# Fpga.net
KiCad netlist of a schematic drawn in Altium Designer
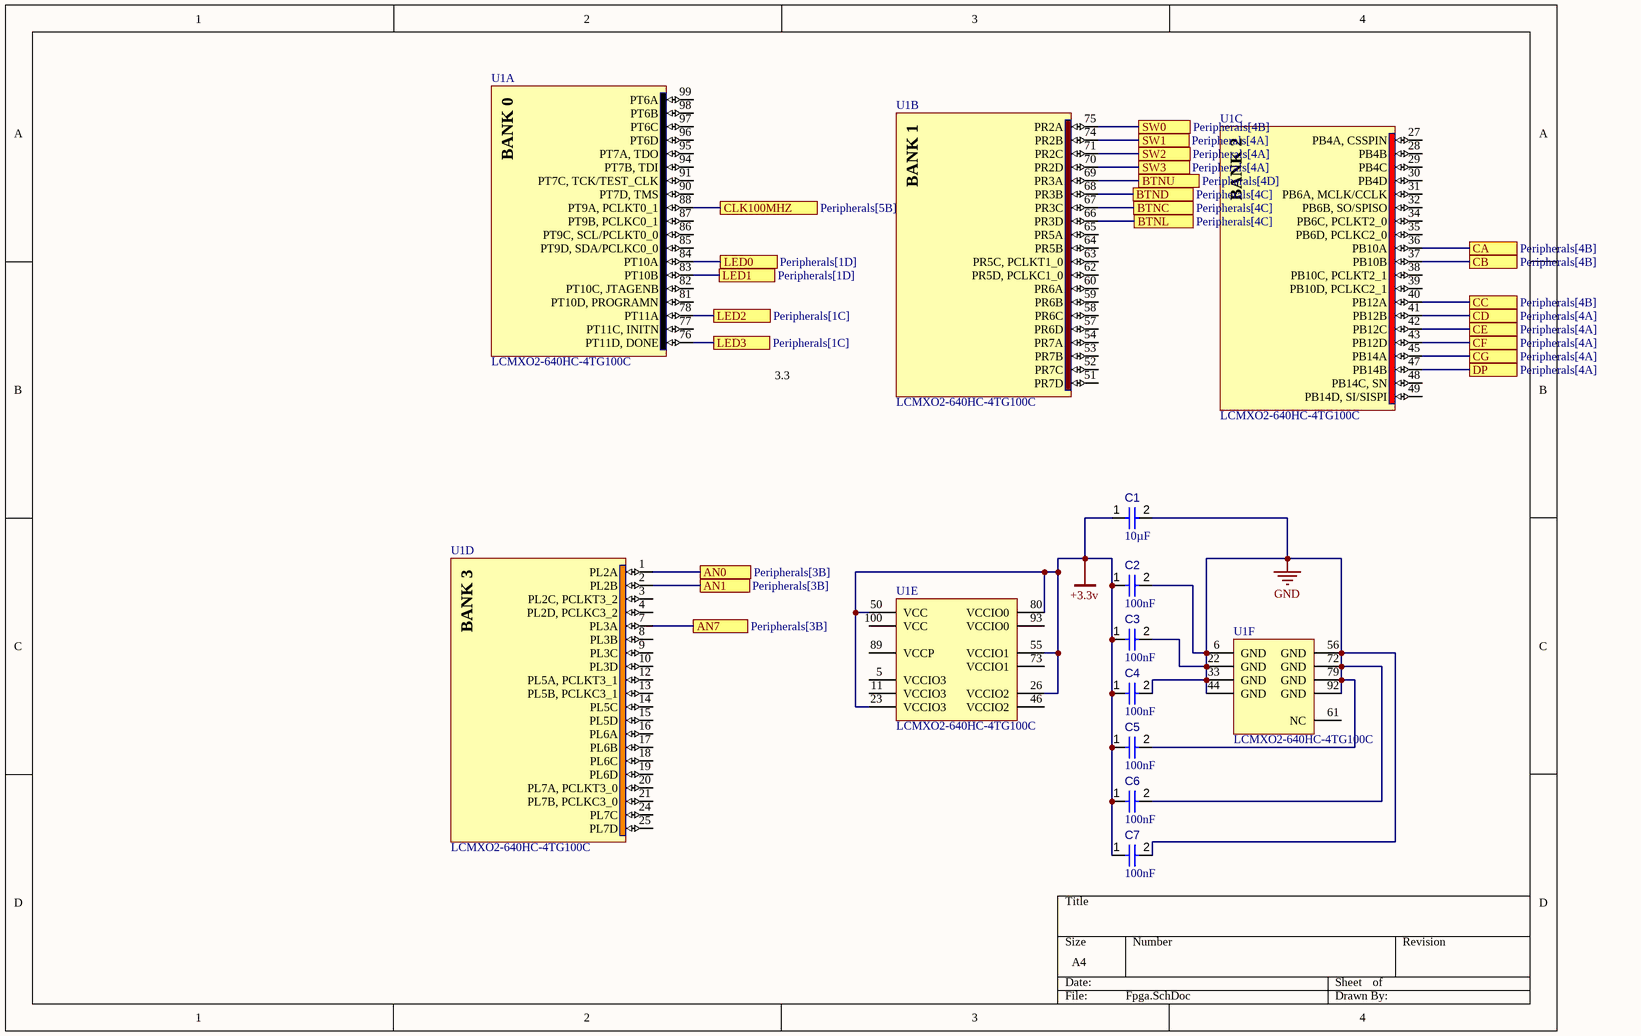
[diagram p0: Fpga.SchDoc]

(export (version "E")
  (design (tool "Eeschema 10.0.6"))
  (components
    (comp (ref "C1")
      (value "10µF")
      (footprint "CAPC0805(2012)145_L")
      (description "Chip Capacitor, 10µF +/-20%, 25V, 0805, Thickness 1.45 mm")
      (fields (field (name "TOLERANCE") "10%") (field (name "Comment") "Capacitor 10µF +/-20% 25V 0805"))
      (libsource (lib "Md-arman-zaid Efty") (part "CAP-NP-2"))
    )
    (comp (ref "C2")
      (value "100nF")
      (footprint "CAPC0402(1005)60_L")
      (description "Chip Capacitor, 100nF +/-20%, 10V, 0402, Thickness 0.6 mm")
      (fields (field (name "TOLERANCE") "20%") (field (name "Comment") "Capacitor 100nF +/-20% 10V 0402"))
      (libsource (lib "Md-arman-zaid Efty") (part "CAP-NP-2"))
    )
    (comp (ref "C3")
      (value "100nF")
      (footprint "CAPC0402(1005)60_L")
      (description "Chip Capacitor, 100nF +/-20%, 10V, 0402, Thickness 0.6 mm")
      (fields (field (name "TOLERANCE") "20%") (field (name "Comment") "Capacitor 100nF +/-20% 10V 0402"))
      (libsource (lib "Md-arman-zaid Efty") (part "CAP-NP-2"))
    )
    (comp (ref "C4")
      (value "100nF")
      (footprint "CAPC0402(1005)60_L")
      (description "Chip Capacitor, 100nF +/-20%, 10V, 0402, Thickness 0.6 mm")
      (fields (field (name "TOLERANCE") "20%") (field (name "Comment") "Capacitor 100nF +/-20% 10V 0402"))
      (libsource (lib "Md-arman-zaid Efty") (part "CAP-NP-2"))
    )
    (comp (ref "C5")
      (value "100nF")
      (footprint "CAPC0402(1005)60_L")
      (description "Chip Capacitor, 100nF +/-20%, 10V, 0402, Thickness 0.6 mm")
      (fields (field (name "TOLERANCE") "20%") (field (name "Comment") "Capacitor 100nF +/-20% 10V 0402"))
      (libsource (lib "Md-arman-zaid Efty") (part "CAP-NP-2"))
    )
    (comp (ref "C6")
      (value "100nF")
      (footprint "CAPC0402(1005)60_L")
      (description "Chip Capacitor, 100nF +/-20%, 10V, 0402, Thickness 0.6 mm")
      (fields (field (name "TOLERANCE") "20%") (field (name "Comment") "Capacitor 100nF +/-20% 10V 0402"))
      (libsource (lib "Md-arman-zaid Efty") (part "CAP-NP-2"))
    )
    (comp (ref "C7")
      (value "100nF")
      (footprint "CAPC0402(1005)60_L")
      (description "Chip Capacitor, 100nF +/-20%, 10V, 0402, Thickness 0.6 mm")
      (fields (field (name "TOLERANCE") "20%") (field (name "Comment") "Capacitor 100nF +/-20% 10V 0402"))
      (libsource (lib "Md-arman-zaid Efty") (part "CAP-NP-2"))
    )
    (comp (ref "U1")
      (value "LCMXO2-640HC-4TG100C")
      (footprint "TQFP100_M")
      (libsource (lib "Altium Content Vault") (part "PLD-LTMXO2-640-TQ100"))
    )
  )
  (nets
    (net (code "1") (name "+3.3v") (class "Default")
      (node (ref "C1") (pin "1") (pinfunction "1_1") (pintype "passive"))
      (node (ref "C2") (pin "1") (pinfunction "1_1") (pintype "passive"))
      (node (ref "C3") (pin "1") (pinfunction "1_1") (pintype "passive"))
      (node (ref "C4") (pin "1") (pinfunction "1_1") (pintype "passive"))
      (node (ref "C5") (pin "1") (pinfunction "1_1") (pintype "passive"))
      (node (ref "C6") (pin "1") (pinfunction "1_1") (pintype "passive"))
      (node (ref "C7") (pin "1") (pinfunction "1_1") (pintype "passive"))
      (node (ref "U1") (pin "23") (pinfunction "VCCIO3_23") (pintype "power_in"))
      (node (ref "U1") (pin "26") (pinfunction "VCCIO2_26") (pintype "power_in"))
      (node (ref "U1") (pin "50") (pinfunction "VCC_50") (pintype "power_in"))
      (node (ref "U1") (pin "55") (pinfunction "VCCIO1_55") (pintype "power_in"))
      (node (ref "U1") (pin "80") (pinfunction "VCCIO0_80") (pintype "power_in"))
    )
    (net (code "2") (name "/AN0") (class "Default")
      (node (ref "U1") (pin "1") (pinfunction "PL2A_1") (pintype "bidirectional"))
    )
    (net (code "3") (name "/AN1") (class "Default")
      (node (ref "U1") (pin "2") (pinfunction "PL2B_2") (pintype "bidirectional"))
    )
    (net (code "4") (name "/AN7") (class "Default")
      (node (ref "U1") (pin "7") (pinfunction "PL3A_7") (pintype "bidirectional"))
    )
    (net (code "5") (name "/BTNC") (class "Default")
      (node (ref "U1") (pin "67") (pinfunction "PR3C_67") (pintype "bidirectional"))
    )
    (net (code "6") (name "/BTND") (class "Default")
      (node (ref "U1") (pin "68") (pinfunction "PR3B_68") (pintype "bidirectional"))
    )
    (net (code "7") (name "/BTNL") (class "Default")
      (node (ref "U1") (pin "66") (pinfunction "PR3D_66") (pintype "bidirectional"))
    )
    (net (code "8") (name "/BTNU") (class "Default")
      (node (ref "U1") (pin "69") (pinfunction "PR3A_69") (pintype "bidirectional"))
    )
    (net (code "9") (name "/CA") (class "Default")
      (node (ref "U1") (pin "36") (pinfunction "PB10A_36") (pintype "bidirectional"))
    )
    (net (code "10") (name "/CB") (class "Default")
      (node (ref "U1") (pin "37") (pinfunction "PB10B_37") (pintype "bidirectional"))
    )
    (net (code "11") (name "/CC") (class "Default")
      (node (ref "U1") (pin "40") (pinfunction "PB12A_40") (pintype "bidirectional"))
    )
    (net (code "12") (name "/CD") (class "Default")
      (node (ref "U1") (pin "41") (pinfunction "PB12B_41") (pintype "bidirectional"))
    )
    (net (code "13") (name "/CE") (class "Default")
      (node (ref "U1") (pin "42") (pinfunction "PB12C_42") (pintype "bidirectional"))
    )
    (net (code "14") (name "/CF") (class "Default")
      (node (ref "U1") (pin "43") (pinfunction "PB12D_43") (pintype "bidirectional"))
    )
    (net (code "15") (name "/CG") (class "Default")
      (node (ref "U1") (pin "45") (pinfunction "PB14A_45") (pintype "bidirectional"))
    )
    (net (code "16") (name "/CLK100MHZ") (class "Default")
      (node (ref "U1") (pin "88") (pinfunction "PT9A,_PCLKT0_1_88") (pintype "bidirectional"))
    )
    (net (code "17") (name "/DP") (class "Default")
      (node (ref "U1") (pin "47") (pinfunction "PB14B_47") (pintype "bidirectional"))
    )
    (net (code "18") (name "/LED0") (class "Default")
      (node (ref "U1") (pin "84") (pinfunction "PT10A_84") (pintype "bidirectional"))
    )
    (net (code "19") (name "/LED1") (class "Default")
      (node (ref "U1") (pin "83") (pinfunction "PT10B_83") (pintype "bidirectional"))
    )
    (net (code "20") (name "/LED2") (class "Default")
      (node (ref "U1") (pin "78") (pinfunction "PT11A_78") (pintype "bidirectional"))
    )
    (net (code "21") (name "/LED3") (class "Default")
      (node (ref "U1") (pin "76") (pinfunction "PT11D,_DONE_76") (pintype "bidirectional"))
    )
    (net (code "22") (name "/SW0") (class "Default")
      (node (ref "U1") (pin "75") (pinfunction "PR2A_75") (pintype "bidirectional"))
    )
    (net (code "23") (name "/SW1") (class "Default")
      (node (ref "U1") (pin "74") (pinfunction "PR2B_74") (pintype "bidirectional"))
    )
    (net (code "24") (name "/SW2") (class "Default")
      (node (ref "U1") (pin "71") (pinfunction "PR2C_71") (pintype "bidirectional"))
    )
    (net (code "25") (name "/SW3") (class "Default")
      (node (ref "U1") (pin "70") (pinfunction "PR2D_70") (pintype "bidirectional"))
    )
    (net (code "26") (name "GND") (class "Default")
      (node (ref "C1") (pin "2") (pinfunction "2_2") (pintype "passive"))
      (node (ref "C2") (pin "2") (pinfunction "2_2") (pintype "passive"))
      (node (ref "C3") (pin "2") (pinfunction "2_2") (pintype "passive"))
      (node (ref "C4") (pin "2") (pinfunction "2_2") (pintype "passive"))
      (node (ref "C5") (pin "2") (pinfunction "2_2") (pintype "passive"))
      (node (ref "C6") (pin "2") (pinfunction "2_2") (pintype "passive"))
      (node (ref "C7") (pin "2") (pinfunction "2_2") (pintype "passive"))
      (node (ref "U1") (pin "22") (pinfunction "GND_22") (pintype "power_in"))
      (node (ref "U1") (pin "33") (pinfunction "GND_33") (pintype "power_in"))
      (node (ref "U1") (pin "44") (pinfunction "GND_44") (pintype "power_in"))
      (node (ref "U1") (pin "56") (pinfunction "GND_56") (pintype "power_in"))
      (node (ref "U1") (pin "6") (pinfunction "GND_6") (pintype "power_in"))
      (node (ref "U1") (pin "72") (pinfunction "GND_72") (pintype "power_in"))
      (node (ref "U1") (pin "79") (pinfunction "GND_79") (pintype "power_in"))
      (node (ref "U1") (pin "92") (pinfunction "GND_92") (pintype "power_in"))
    )
    (net (code "27") (name "unconnected-(U1A-PT6A-Pad99)") (class "Default")
      (node (ref "U1") (pin "99") (pinfunction "PT6A_99") (pintype "bidirectional"))
    )
    (net (code "28") (name "unconnected-(U1A-PT6B-Pad98)") (class "Default")
      (node (ref "U1") (pin "98") (pinfunction "PT6B_98") (pintype "bidirectional"))
    )
    (net (code "29") (name "unconnected-(U1A-PT6C-Pad97)") (class "Default")
      (node (ref "U1") (pin "97") (pinfunction "PT6C_97") (pintype "bidirectional"))
    )
    (net (code "30") (name "unconnected-(U1A-PT6D-Pad96)") (class "Default")
      (node (ref "U1") (pin "96") (pinfunction "PT6D_96") (pintype "bidirectional"))
    )
    (net (code "31") (name "unconnected-(U1A-PT7A,_TDO-Pad95)") (class "Default")
      (node (ref "U1") (pin "95") (pinfunction "PT7A,_TDO_95") (pintype "bidirectional"))
    )
    (net (code "32") (name "unconnected-(U1A-PT7B,_TDI-Pad94)") (class "Default")
      (node (ref "U1") (pin "94") (pinfunction "PT7B,_TDI_94") (pintype "bidirectional"))
    )
    (net (code "33") (name "unconnected-(U1A-PT7C,_TCK{slash}TEST_CLK-Pad91)") (class "Default")
      (node (ref "U1") (pin "91") (pinfunction "PT7C,_TCK/TEST_CLK_91") (pintype "bidirectional"))
    )
    (net (code "34") (name "unconnected-(U1A-PT7D,_TMS-Pad90)") (class "Default")
      (node (ref "U1") (pin "90") (pinfunction "PT7D,_TMS_90") (pintype "bidirectional"))
    )
    (net (code "35") (name "unconnected-(U1A-PT9B,_PCLKC0_1-Pad87)") (class "Default")
      (node (ref "U1") (pin "87") (pinfunction "PT9B,_PCLKC0_1_87") (pintype "bidirectional"))
    )
    (net (code "36") (name "unconnected-(U1A-PT9C,_SCL{slash}PCLKT0_0-Pad86)") (class "Default")
      (node (ref "U1") (pin "86") (pinfunction "PT9C,_SCL/PCLKT0_0_86") (pintype "bidirectional"))
    )
    (net (code "37") (name "unconnected-(U1A-PT9D,_SDA{slash}PCLKC0_0-Pad85)") (class "Default")
      (node (ref "U1") (pin "85") (pinfunction "PT9D,_SDA/PCLKC0_0_85") (pintype "bidirectional"))
    )
    (net (code "38") (name "unconnected-(U1A-PT10C,_JTAGENB-Pad82)") (class "Default")
      (node (ref "U1") (pin "82") (pinfunction "PT10C,_JTAGENB_82") (pintype "bidirectional"))
    )
    (net (code "39") (name "unconnected-(U1A-PT10D,_PROGRAMN-Pad81)") (class "Default")
      (node (ref "U1") (pin "81") (pinfunction "PT10D,_PROGRAMN_81") (pintype "bidirectional"))
    )
    (net (code "40") (name "unconnected-(U1A-PT11C,_INITN-Pad77)") (class "Default")
      (node (ref "U1") (pin "77") (pinfunction "PT11C,_INITN_77") (pintype "bidirectional"))
    )
    (net (code "41") (name "unconnected-(U1B-PR5A-Pad65)") (class "Default")
      (node (ref "U1") (pin "65") (pinfunction "PR5A_65") (pintype "bidirectional"))
    )
    (net (code "42") (name "unconnected-(U1B-PR5B-Pad64)") (class "Default")
      (node (ref "U1") (pin "64") (pinfunction "PR5B_64") (pintype "bidirectional"))
    )
    (net (code "43") (name "unconnected-(U1B-PR5C,_PCLKT1_0-Pad63)") (class "Default")
      (node (ref "U1") (pin "63") (pinfunction "PR5C,_PCLKT1_0_63") (pintype "bidirectional"))
    )
    (net (code "44") (name "unconnected-(U1B-PR5D,_PCLKC1_0-Pad62)") (class "Default")
      (node (ref "U1") (pin "62") (pinfunction "PR5D,_PCLKC1_0_62") (pintype "bidirectional"))
    )
    (net (code "45") (name "unconnected-(U1B-PR6A-Pad60)") (class "Default")
      (node (ref "U1") (pin "60") (pinfunction "PR6A_60") (pintype "bidirectional"))
    )
    (net (code "46") (name "unconnected-(U1B-PR6B-Pad59)") (class "Default")
      (node (ref "U1") (pin "59") (pinfunction "PR6B_59") (pintype "bidirectional"))
    )
    (net (code "47") (name "unconnected-(U1B-PR6C-Pad58)") (class "Default")
      (node (ref "U1") (pin "58") (pinfunction "PR6C_58") (pintype "bidirectional"))
    )
    (net (code "48") (name "unconnected-(U1B-PR6D-Pad57)") (class "Default")
      (node (ref "U1") (pin "57") (pinfunction "PR6D_57") (pintype "bidirectional"))
    )
    (net (code "49") (name "unconnected-(U1B-PR7A-Pad54)") (class "Default")
      (node (ref "U1") (pin "54") (pinfunction "PR7A_54") (pintype "bidirectional"))
    )
    (net (code "50") (name "unconnected-(U1B-PR7B-Pad53)") (class "Default")
      (node (ref "U1") (pin "53") (pinfunction "PR7B_53") (pintype "bidirectional"))
    )
    (net (code "51") (name "unconnected-(U1B-PR7C-Pad52)") (class "Default")
      (node (ref "U1") (pin "52") (pinfunction "PR7C_52") (pintype "bidirectional"))
    )
    (net (code "52") (name "unconnected-(U1B-PR7D-Pad51)") (class "Default")
      (node (ref "U1") (pin "51") (pinfunction "PR7D_51") (pintype "bidirectional"))
    )
    (net (code "53") (name "unconnected-(U1C-PB4A,_CSSPIN-Pad27)") (class "Default")
      (node (ref "U1") (pin "27") (pinfunction "PB4A,_CSSPIN_27") (pintype "bidirectional"))
    )
    (net (code "54") (name "unconnected-(U1C-PB4B-Pad28)") (class "Default")
      (node (ref "U1") (pin "28") (pinfunction "PB4B_28") (pintype "bidirectional"))
    )
    (net (code "55") (name "unconnected-(U1C-PB4C-Pad29)") (class "Default")
      (node (ref "U1") (pin "29") (pinfunction "PB4C_29") (pintype "bidirectional"))
    )
    (net (code "56") (name "unconnected-(U1C-PB4D-Pad30)") (class "Default")
      (node (ref "U1") (pin "30") (pinfunction "PB4D_30") (pintype "bidirectional"))
    )
    (net (code "57") (name "unconnected-(U1C-PB6A,_MCLK{slash}CCLK-Pad31)") (class "Default")
      (node (ref "U1") (pin "31") (pinfunction "PB6A,_MCLK/CCLK_31") (pintype "bidirectional"))
    )
    (net (code "58") (name "unconnected-(U1C-PB6B,_SO{slash}SPISO-Pad32)") (class "Default")
      (node (ref "U1") (pin "32") (pinfunction "PB6B,_SO/SPISO_32") (pintype "bidirectional"))
    )
    (net (code "59") (name "unconnected-(U1C-PB6C,_PCLKT2_0-Pad34)") (class "Default")
      (node (ref "U1") (pin "34") (pinfunction "PB6C,_PCLKT2_0_34") (pintype "bidirectional"))
    )
    (net (code "60") (name "unconnected-(U1C-PB6D,_PCLKC2_0-Pad35)") (class "Default")
      (node (ref "U1") (pin "35") (pinfunction "PB6D,_PCLKC2_0_35") (pintype "bidirectional"))
    )
    (net (code "61") (name "unconnected-(U1C-PB10C,_PCLKT2_1-Pad38)") (class "Default")
      (node (ref "U1") (pin "38") (pinfunction "PB10C,_PCLKT2_1_38") (pintype "bidirectional"))
    )
    (net (code "62") (name "unconnected-(U1C-PB10D,_PCLKC2_1-Pad39)") (class "Default")
      (node (ref "U1") (pin "39") (pinfunction "PB10D,_PCLKC2_1_39") (pintype "bidirectional"))
    )
    (net (code "63") (name "unconnected-(U1C-PB14C,_SN-Pad48)") (class "Default")
      (node (ref "U1") (pin "48") (pinfunction "PB14C,_SN_48") (pintype "bidirectional"))
    )
    (net (code "64") (name "unconnected-(U1C-PB14D,_SI{slash}SISPI-Pad49)") (class "Default")
      (node (ref "U1") (pin "49") (pinfunction "PB14D,_SI/SISPI_49") (pintype "bidirectional"))
    )
    (net (code "65") (name "unconnected-(U1D-PL2C,_PCLKT3_2-Pad3)") (class "Default")
      (node (ref "U1") (pin "3") (pinfunction "PL2C,_PCLKT3_2_3") (pintype "bidirectional"))
    )
    (net (code "66") (name "unconnected-(U1D-PL2D,_PCLKC3_2-Pad4)") (class "Default")
      (node (ref "U1") (pin "4") (pinfunction "PL2D,_PCLKC3_2_4") (pintype "bidirectional"))
    )
    (net (code "67") (name "unconnected-(U1D-PL3B-Pad8)") (class "Default")
      (node (ref "U1") (pin "8") (pinfunction "PL3B_8") (pintype "bidirectional"))
    )
    (net (code "68") (name "unconnected-(U1D-PL3C-Pad9)") (class "Default")
      (node (ref "U1") (pin "9") (pinfunction "PL3C_9") (pintype "bidirectional"))
    )
    (net (code "69") (name "unconnected-(U1D-PL3D-Pad10)") (class "Default")
      (node (ref "U1") (pin "10") (pinfunction "PL3D_10") (pintype "bidirectional"))
    )
    (net (code "70") (name "unconnected-(U1D-PL5A,_PCLKT3_1-Pad12)") (class "Default")
      (node (ref "U1") (pin "12") (pinfunction "PL5A,_PCLKT3_1_12") (pintype "bidirectional"))
    )
    (net (code "71") (name "unconnected-(U1D-PL5B,_PCLKC3_1-Pad13)") (class "Default")
      (node (ref "U1") (pin "13") (pinfunction "PL5B,_PCLKC3_1_13") (pintype "bidirectional"))
    )
    (net (code "72") (name "unconnected-(U1D-PL5C-Pad14)") (class "Default")
      (node (ref "U1") (pin "14") (pinfunction "PL5C_14") (pintype "bidirectional"))
    )
    (net (code "73") (name "unconnected-(U1D-PL5D-Pad15)") (class "Default")
      (node (ref "U1") (pin "15") (pinfunction "PL5D_15") (pintype "bidirectional"))
    )
    (net (code "74") (name "unconnected-(U1D-PL6A-Pad16)") (class "Default")
      (node (ref "U1") (pin "16") (pinfunction "PL6A_16") (pintype "bidirectional"))
    )
    (net (code "75") (name "unconnected-(U1D-PL6B-Pad17)") (class "Default")
      (node (ref "U1") (pin "17") (pinfunction "PL6B_17") (pintype "bidirectional"))
    )
    (net (code "76") (name "unconnected-(U1D-PL6C-Pad18)") (class "Default")
      (node (ref "U1") (pin "18") (pinfunction "PL6C_18") (pintype "bidirectional"))
    )
    (net (code "77") (name "unconnected-(U1D-PL6D-Pad19)") (class "Default")
      (node (ref "U1") (pin "19") (pinfunction "PL6D_19") (pintype "bidirectional"))
    )
    (net (code "78") (name "unconnected-(U1D-PL7A,_PCLKT3_0-Pad20)") (class "Default")
      (node (ref "U1") (pin "20") (pinfunction "PL7A,_PCLKT3_0_20") (pintype "bidirectional"))
    )
    (net (code "79") (name "unconnected-(U1D-PL7B,_PCLKC3_0-Pad21)") (class "Default")
      (node (ref "U1") (pin "21") (pinfunction "PL7B,_PCLKC3_0_21") (pintype "bidirectional"))
    )
    (net (code "80") (name "unconnected-(U1D-PL7C-Pad24)") (class "Default")
      (node (ref "U1") (pin "24") (pinfunction "PL7C_24") (pintype "bidirectional"))
    )
    (net (code "81") (name "unconnected-(U1D-PL7D-Pad25)") (class "Default")
      (node (ref "U1") (pin "25") (pinfunction "PL7D_25") (pintype "bidirectional"))
    )
    (net (code "82") (name "unconnected-(U1E-VCC-Pad100)") (class "Default")
      (node (ref "U1") (pin "100") (pinfunction "VCC_100") (pintype "power_in"))
    )
    (net (code "83") (name "unconnected-(U1E-VCCIO0-Pad93)") (class "Default")
      (node (ref "U1") (pin "93") (pinfunction "VCCIO0_93") (pintype "power_in"))
    )
    (net (code "84") (name "unconnected-(U1E-VCCIO1-Pad73)") (class "Default")
      (node (ref "U1") (pin "73") (pinfunction "VCCIO1_73") (pintype "power_in"))
    )
    (net (code "85") (name "unconnected-(U1E-VCCIO2-Pad46)") (class "Default")
      (node (ref "U1") (pin "46") (pinfunction "VCCIO2_46") (pintype "power_in"))
    )
    (net (code "86") (name "unconnected-(U1E-VCCIO3-Pad5)") (class "Default")
      (node (ref "U1") (pin "5") (pinfunction "VCCIO3_5") (pintype "power_in"))
    )
    (net (code "87") (name "unconnected-(U1E-VCCIO3-Pad11)") (class "Default")
      (node (ref "U1") (pin "11") (pinfunction "VCCIO3_11") (pintype "power_in"))
    )
    (net (code "88") (name "unconnected-(U1E-VCCP-Pad89)") (class "Default")
      (node (ref "U1") (pin "89") (pinfunction "VCCP_89") (pintype "power_in"))
    )
    (net (code "89") (name "unconnected-(U1F-NC-Pad61)") (class "Default")
      (node (ref "U1") (pin "61") (pinfunction "NC_61") (pintype "passive"))
    )
  )
)
